# Motherboard_lpcxpresso.net
KiCad netlist of a schematic drawn in EAGLE
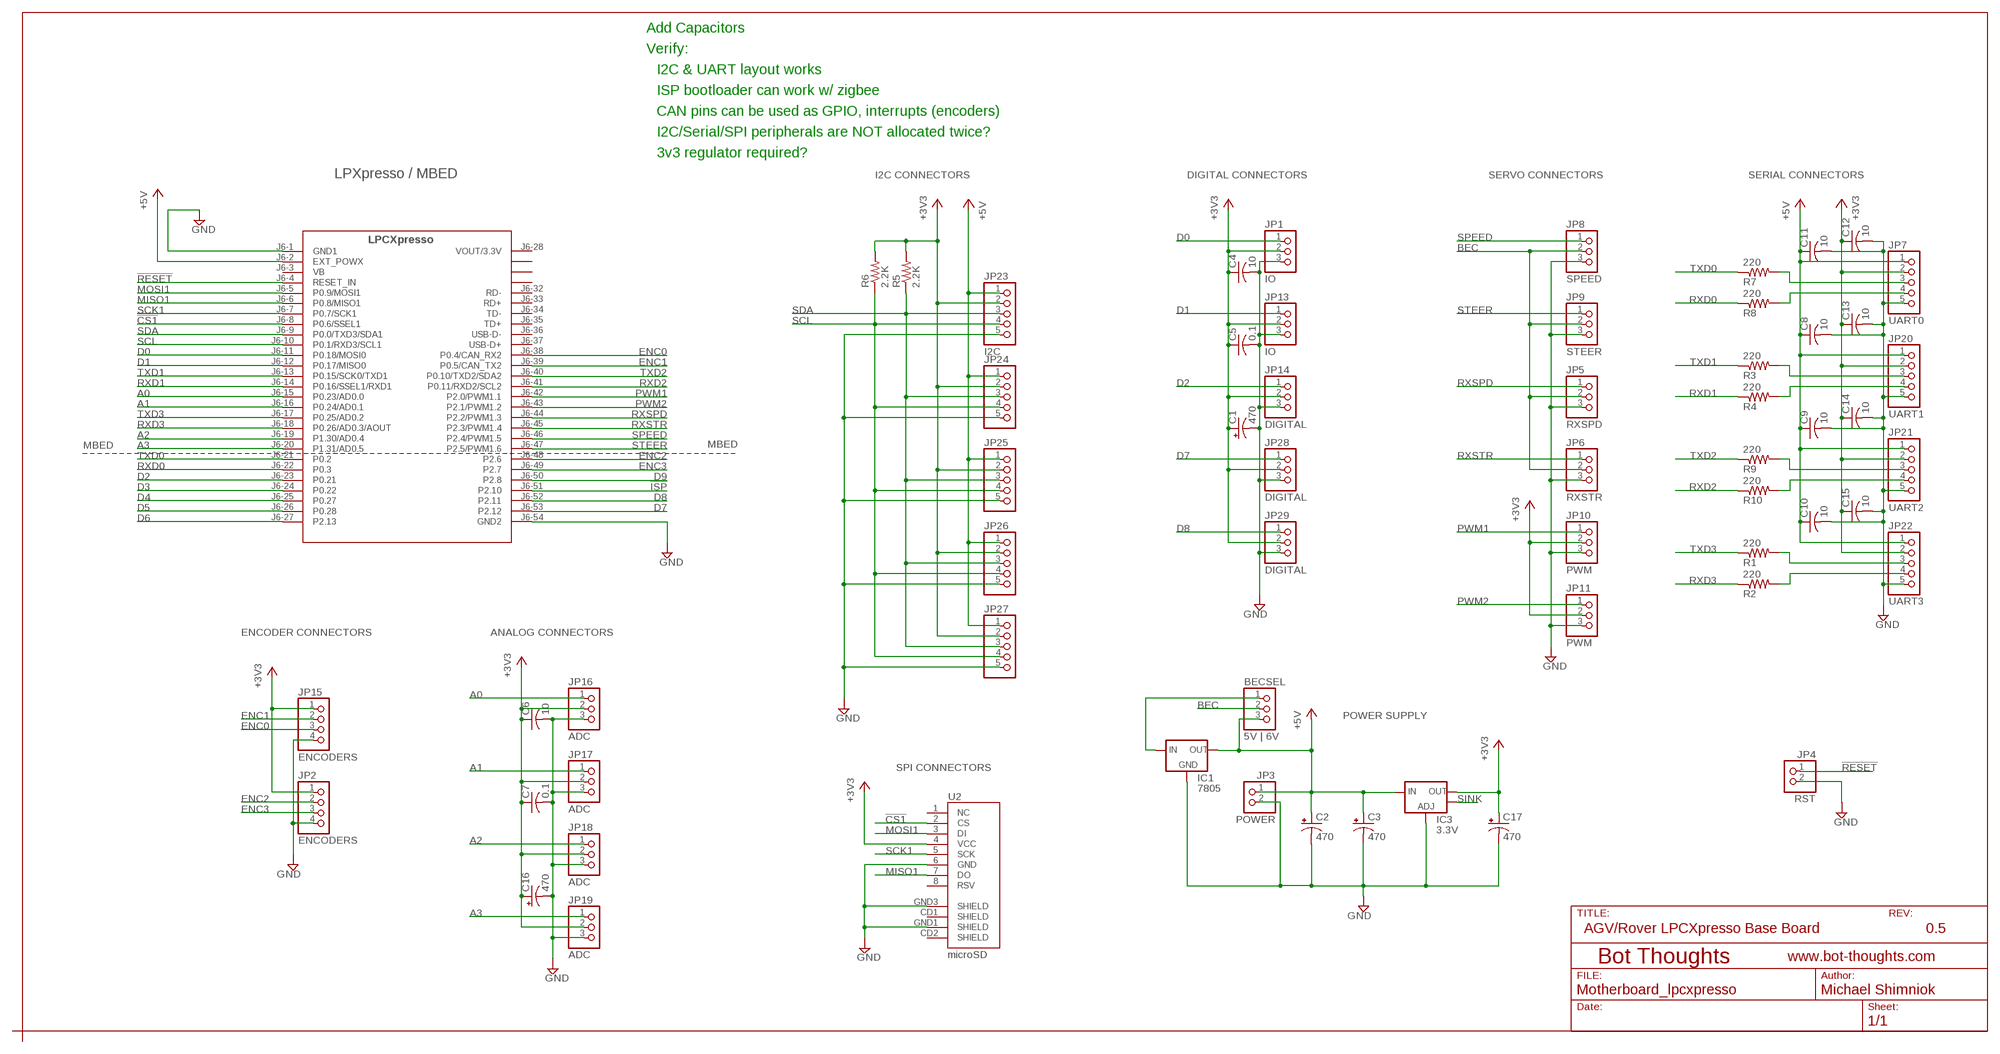
[diagram p0: schematic, sheet 1]

(export (version "E")
  (design (tool "Eeschema 10.0.6"))
  (components
    (comp (ref "BECSEL")
      (value "5V | 6V")
      (footprint "eagle-import:1X03-S")
      (libsource (lib "eagle-import") (part "PINHD-1X03_2.54-S"))
    )
    (comp (ref "C1")
      (value "470")
      (footprint "eagle-import:SMC_C")
      (libsource (lib "eagle-import") (part "CAP_POL_SMC_C"))
    )
    (comp (ref "C2")
      (value "470")
      (footprint "eagle-import:SMC_C")
      (libsource (lib "eagle-import") (part "CAP_POL_SMC_C"))
    )
    (comp (ref "C3")
      (value "470")
      (footprint "eagle-import:SMC_C")
      (libsource (lib "eagle-import") (part "CAP_POL_SMC_C"))
    )
    (comp (ref "C4")
      (value "10")
      (footprint "eagle-import:C0603")
      (libsource (lib "eagle-import") (part "C-USC0603"))
    )
    (comp (ref "C5")
      (value "0.1")
      (footprint "eagle-import:C0603")
      (libsource (lib "eagle-import") (part "C-USC0603"))
    )
    (comp (ref "C6")
      (value "10")
      (footprint "eagle-import:C0603")
      (libsource (lib "eagle-import") (part "C-USC0603"))
    )
    (comp (ref "C7")
      (value "0.1")
      (footprint "eagle-import:C0603")
      (libsource (lib "eagle-import") (part "C-USC0603"))
    )
    (comp (ref "C8")
      (value "10")
      (footprint "eagle-import:C0603")
      (libsource (lib "eagle-import") (part "C-USC0603"))
    )
    (comp (ref "C9")
      (value "10")
      (footprint "eagle-import:C0603")
      (libsource (lib "eagle-import") (part "C-USC0603"))
    )
    (comp (ref "C10")
      (value "10")
      (footprint "eagle-import:C0603")
      (libsource (lib "eagle-import") (part "C-USC0603"))
    )
    (comp (ref "C11")
      (value "10")
      (footprint "eagle-import:C0603")
      (libsource (lib "eagle-import") (part "C-USC0603"))
    )
    (comp (ref "C12")
      (value "10")
      (footprint "eagle-import:C0603")
      (libsource (lib "eagle-import") (part "C-USC0603"))
    )
    (comp (ref "C13")
      (value "10")
      (footprint "eagle-import:C0603")
      (libsource (lib "eagle-import") (part "C-USC0603"))
    )
    (comp (ref "C14")
      (value "10")
      (footprint "eagle-import:C0603")
      (libsource (lib "eagle-import") (part "C-USC0603"))
    )
    (comp (ref "C15")
      (value "10")
      (footprint "eagle-import:C0603")
      (libsource (lib "eagle-import") (part "C-USC0603"))
    )
    (comp (ref "C16")
      (value "470")
      (footprint "eagle-import:SMC_C")
      (libsource (lib "eagle-import") (part "CAP_POL_SMC_C"))
    )
    (comp (ref "C17")
      (value "470")
      (footprint "eagle-import:SMC_C")
      (libsource (lib "eagle-import") (part "CAP_POL_SMC_C"))
    )
    (comp (ref "IC1")
      (value "7805")
      (footprint "eagle-import:78XXS")
      (libsource (lib "eagle-import") (part "78XXS"))
    )
    (comp (ref "IC3")
      (value "3.3V")
      (footprint "eagle-import:SOT223")
      (libsource (lib "eagle-import") (part "V_REG_LM1117SOT223"))
    )
    (comp (ref "JP1")
      (value "IO")
      (footprint "eagle-import:1X03-S")
      (libsource (lib "eagle-import") (part "PINHD-1X03_2.54-S"))
    )
    (comp (ref "JP2")
      (value "ENCODERS")
      (footprint "eagle-import:1X04-S")
      (libsource (lib "eagle-import") (part "PINHD-1X04_2.54-S"))
    )
    (comp (ref "JP3")
      (value "POWER")
      (footprint "eagle-import:1X02-S")
      (libsource (lib "eagle-import") (part "PINHD-1X02_2.54-S"))
    )
    (comp (ref "JP4")
      (value "RST")
      (footprint "eagle-import:1X02-S")
      (libsource (lib "eagle-import") (part "PINHD-1X02_2.54-S"))
    )
    (comp (ref "JP5")
      (value "RXSPD")
      (footprint "eagle-import:1X03-S")
      (libsource (lib "eagle-import") (part "PINHD-1X03_2.54-S"))
    )
    (comp (ref "JP6")
      (value "RXSTR")
      (footprint "eagle-import:1X03-S")
      (libsource (lib "eagle-import") (part "PINHD-1X03_2.54-S"))
    )
    (comp (ref "JP7")
      (value "UART0")
      (footprint "eagle-import:1X05-S")
      (libsource (lib "eagle-import") (part "PINHD-1X05_2.54-S"))
    )
    (comp (ref "JP8")
      (value "SPEED")
      (footprint "eagle-import:1X03-S")
      (libsource (lib "eagle-import") (part "PINHD-1X03_2.54-S"))
    )
    (comp (ref "JP9")
      (value "STEER")
      (footprint "eagle-import:1X03-S")
      (libsource (lib "eagle-import") (part "PINHD-1X03_2.54-S"))
    )
    (comp (ref "JP10")
      (value "PWM")
      (footprint "eagle-import:1X03-S")
      (libsource (lib "eagle-import") (part "PINHD-1X03_2.54-S"))
    )
    (comp (ref "JP11")
      (value "PWM")
      (footprint "eagle-import:1X03-S")
      (libsource (lib "eagle-import") (part "PINHD-1X03_2.54-S"))
    )
    (comp (ref "JP13")
      (value "IO")
      (footprint "eagle-import:1X03-S")
      (libsource (lib "eagle-import") (part "PINHD-1X03_2.54-S"))
    )
    (comp (ref "JP14")
      (value "DIGITAL")
      (footprint "eagle-import:1X03-S")
      (libsource (lib "eagle-import") (part "PINHD-1X03_2.54-S"))
    )
    (comp (ref "JP15")
      (value "ENCODERS")
      (footprint "eagle-import:1X04-S")
      (libsource (lib "eagle-import") (part "PINHD-1X04_2.54-S"))
    )
    (comp (ref "JP16")
      (value "ADC")
      (footprint "eagle-import:1X03-S")
      (libsource (lib "eagle-import") (part "PINHD-1X03_2.54-S"))
    )
    (comp (ref "JP17")
      (value "ADC")
      (footprint "eagle-import:1X03-S")
      (libsource (lib "eagle-import") (part "PINHD-1X03_2.54-S"))
    )
    (comp (ref "JP18")
      (value "ADC")
      (footprint "eagle-import:1X03-S")
      (libsource (lib "eagle-import") (part "PINHD-1X03_2.54-S"))
    )
    (comp (ref "JP19")
      (value "ADC")
      (footprint "eagle-import:1X03-S")
      (libsource (lib "eagle-import") (part "PINHD-1X03_2.54-S"))
    )
    (comp (ref "JP20")
      (value "UART1")
      (footprint "eagle-import:1X05-S")
      (libsource (lib "eagle-import") (part "PINHD-1X05_2.54-S"))
    )
    (comp (ref "JP21")
      (value "UART2")
      (footprint "eagle-import:1X05-S")
      (libsource (lib "eagle-import") (part "PINHD-1X05_2.54-S"))
    )
    (comp (ref "JP22")
      (value "UART3")
      (footprint "eagle-import:1X05-S")
      (libsource (lib "eagle-import") (part "PINHD-1X05_2.54-S"))
    )
    (comp (ref "JP23")
      (value "I2C")
      (footprint "eagle-import:1X05-S")
      (libsource (lib "eagle-import") (part "PINHD-1X05_2.54-S"))
    )
    (comp (ref "JP24")
      (value "PINHD-1X05_2.54-S")
      (footprint "eagle-import:1X05-S")
      (libsource (lib "eagle-import") (part "PINHD-1X05_2.54-S"))
    )
    (comp (ref "JP25")
      (value "PINHD-1X05_2.54-S")
      (footprint "eagle-import:1X05-S")
      (libsource (lib "eagle-import") (part "PINHD-1X05_2.54-S"))
    )
    (comp (ref "JP26")
      (value "PINHD-1X05_2.54-S")
      (footprint "eagle-import:1X05-S")
      (libsource (lib "eagle-import") (part "PINHD-1X05_2.54-S"))
    )
    (comp (ref "JP27")
      (value "PINHD-1X05_2.54-S")
      (footprint "eagle-import:1X05-S")
      (libsource (lib "eagle-import") (part "PINHD-1X05_2.54-S"))
    )
    (comp (ref "JP28")
      (value "DIGITAL")
      (footprint "eagle-import:1X03-S")
      (libsource (lib "eagle-import") (part "PINHD-1X03_2.54-S"))
    )
    (comp (ref "JP29")
      (value "DIGITAL")
      (footprint "eagle-import:1X03-S")
      (libsource (lib "eagle-import") (part "PINHD-1X03_2.54-S"))
    )
    (comp (ref "R1")
      (value "220")
      (footprint "eagle-import:R0603")
      (fields (field (name "MPN") "WCR0805-220RFI"))
      (libsource (lib "eagle-import") (part "R-US_R0603"))
    )
    (comp (ref "R2")
      (value "220")
      (footprint "eagle-import:R0603")
      (fields (field (name "MPN") "WCR0805-220RFI"))
      (libsource (lib "eagle-import") (part "R-US_R0603"))
    )
    (comp (ref "R3")
      (value "220")
      (footprint "eagle-import:R0603")
      (fields (field (name "MPN") "WCR0805-220RFI"))
      (libsource (lib "eagle-import") (part "R-US_R0603"))
    )
    (comp (ref "R4")
      (value "220")
      (footprint "eagle-import:R0603")
      (fields (field (name "MPN") "WCR0805-220RFI"))
      (libsource (lib "eagle-import") (part "R-US_R0603"))
    )
    (comp (ref "R5")
      (value "2.2K")
      (footprint "eagle-import:R0603")
      (libsource (lib "eagle-import") (part "R-US_R0603"))
    )
    (comp (ref "R6")
      (value "2.2K")
      (footprint "eagle-import:R0603")
      (libsource (lib "eagle-import") (part "R-US_R0603"))
    )
    (comp (ref "R7")
      (value "220")
      (footprint "eagle-import:R0603")
      (fields (field (name "MPN") "WCR0805-220RFI"))
      (libsource (lib "eagle-import") (part "R-US_R0603"))
    )
    (comp (ref "R8")
      (value "220")
      (footprint "eagle-import:R0603")
      (fields (field (name "MPN") "WCR0805-220RFI"))
      (libsource (lib "eagle-import") (part "R-US_R0603"))
    )
    (comp (ref "R9")
      (value "220")
      (footprint "eagle-import:R0603")
      (fields (field (name "MPN") "WCR0805-220RFI"))
      (libsource (lib "eagle-import") (part "R-US_R0603"))
    )
    (comp (ref "R10")
      (value "220")
      (footprint "eagle-import:R0603")
      (fields (field (name "MPN") "WCR0805-220RFI"))
      (libsource (lib "eagle-import") (part "R-US_R0603"))
    )
    (comp (ref "U$1")
      (value "LPCXPRESSO")
      (footprint "eagle-import:LPCXPRESSO_NO_PAD")
      (libsource (lib "eagle-import") (part "LPCXPRESSO_NO_PAD_1768_REVB"))
    )
    (comp (ref "U2")
      (value "microSD")
      (footprint "eagle-import:MICRO-SD-SOCKET-PP")
      (libsource (lib "eagle-import") (part "USD-SOCKETNEW"))
    )
  )
  (nets
    (net (code "1") (name "+3V3") (class "Default")
      (node (ref "C1") (pin "+") (pinfunction "+_+") (pintype "passive"))
      (node (ref "C12") (pin "1") (pinfunction "1_1") (pintype "passive"))
      (node (ref "C13") (pin "1") (pinfunction "1_1") (pintype "passive"))
      (node (ref "C14") (pin "1") (pinfunction "1_1") (pintype "passive"))
      (node (ref "C15") (pin "1") (pinfunction "1_1") (pintype "passive"))
      (node (ref "C16") (pin "+") (pinfunction "+_+") (pintype "passive"))
      (node (ref "C17") (pin "+") (pinfunction "+_+") (pintype "passive"))
      (node (ref "C4") (pin "1") (pinfunction "1_1") (pintype "passive"))
      (node (ref "C5") (pin "1") (pinfunction "1_1") (pintype "passive"))
      (node (ref "C6") (pin "1") (pinfunction "1_1") (pintype "passive"))
      (node (ref "C7") (pin "1") (pinfunction "1_1") (pintype "passive"))
      (node (ref "IC3") (pin "2") (pinfunction "OUT_2") (pintype "output"))
      (node (ref "JP1") (pin "2") (pinfunction "2_2") (pintype "passive"))
      (node (ref "JP10") (pin "2") (pinfunction "2_2") (pintype "passive"))
      (node (ref "JP11") (pin "2") (pinfunction "2_2") (pintype "passive"))
      (node (ref "JP13") (pin "2") (pinfunction "2_2") (pintype "passive"))
      (node (ref "JP14") (pin "2") (pinfunction "2_2") (pintype "passive"))
      (node (ref "JP15") (pin "1") (pinfunction "1_1") (pintype "passive"))
      (node (ref "JP16") (pin "2") (pinfunction "2_2") (pintype "passive"))
      (node (ref "JP17") (pin "2") (pinfunction "2_2") (pintype "passive"))
      (node (ref "JP18") (pin "2") (pinfunction "2_2") (pintype "passive"))
      (node (ref "JP19") (pin "2") (pinfunction "2_2") (pintype "passive"))
      (node (ref "JP2") (pin "1") (pinfunction "1_1") (pintype "passive"))
      (node (ref "JP20") (pin "2") (pinfunction "2_2") (pintype "passive"))
      (node (ref "JP21") (pin "2") (pinfunction "2_2") (pintype "passive"))
      (node (ref "JP22") (pin "2") (pinfunction "2_2") (pintype "passive"))
      (node (ref "JP23") (pin "2") (pinfunction "2_2") (pintype "passive"))
      (node (ref "JP24") (pin "2") (pinfunction "2_2") (pintype "passive"))
      (node (ref "JP25") (pin "2") (pinfunction "2_2") (pintype "passive"))
      (node (ref "JP26") (pin "2") (pinfunction "2_2") (pintype "passive"))
      (node (ref "JP27") (pin "2") (pinfunction "2_2") (pintype "passive"))
      (node (ref "JP28") (pin "2") (pinfunction "2_2") (pintype "passive"))
      (node (ref "JP29") (pin "2") (pinfunction "2_2") (pintype "passive"))
      (node (ref "JP7") (pin "2") (pinfunction "2_2") (pintype "passive"))
      (node (ref "R5") (pin "2") (pinfunction "2_2") (pintype "passive"))
      (node (ref "R6") (pin "2") (pinfunction "2_2") (pintype "passive"))
      (node (ref "U2") (pin "4") (pinfunction "VCC_4") (pintype "bidirectional"))
    )
    (net (code "2") (name "+5V") (class "Default")
      (node (ref "BECSEL") (pin "3") (pinfunction "3_3") (pintype "passive"))
      (node (ref "C10") (pin "1") (pinfunction "1_1") (pintype "passive"))
      (node (ref "C11") (pin "1") (pinfunction "1_1") (pintype "passive"))
      (node (ref "C2") (pin "+") (pinfunction "+_+") (pintype "passive"))
      (node (ref "C3") (pin "+") (pinfunction "+_+") (pintype "passive"))
      (node (ref "C8") (pin "1") (pinfunction "1_1") (pintype "passive"))
      (node (ref "C9") (pin "1") (pinfunction "1_1") (pintype "passive"))
      (node (ref "IC1") (pin "OUT") (pinfunction "OUT_OUT") (pintype "passive"))
      (node (ref "IC3") (pin "3") (pinfunction "IN_3") (pintype "input"))
      (node (ref "JP20") (pin "1") (pinfunction "1_1") (pintype "passive"))
      (node (ref "JP21") (pin "1") (pinfunction "1_1") (pintype "passive"))
      (node (ref "JP22") (pin "1") (pinfunction "1_1") (pintype "passive"))
      (node (ref "JP23") (pin "1") (pinfunction "1_1") (pintype "passive"))
      (node (ref "JP24") (pin "1") (pinfunction "1_1") (pintype "passive"))
      (node (ref "JP25") (pin "1") (pinfunction "1_1") (pintype "passive"))
      (node (ref "JP26") (pin "1") (pinfunction "1_1") (pintype "passive"))
      (node (ref "JP27") (pin "1") (pinfunction "1_1") (pintype "passive"))
      (node (ref "JP3") (pin "1") (pinfunction "1_1") (pintype "passive"))
      (node (ref "JP7") (pin "1") (pinfunction "1_1") (pintype "passive"))
      (node (ref "U$1") (pin "J6-2") (pinfunction "EXT_POWX_J6-2") (pintype "bidirectional"))
    )
    (net (code "3") (name "/A0") (class "Default")
      (node (ref "JP16") (pin "1") (pinfunction "1_1") (pintype "passive"))
      (node (ref "U$1") (pin "J6-15") (pinfunction "P0.23/AD0.0_J6-15") (pintype "bidirectional"))
    )
    (net (code "4") (name "/A1") (class "Default")
      (node (ref "JP17") (pin "1") (pinfunction "1_1") (pintype "passive"))
      (node (ref "U$1") (pin "J6-16") (pinfunction "P0.24/AD0.1_J6-16") (pintype "bidirectional"))
    )
    (net (code "5") (name "/A2") (class "Default")
      (node (ref "JP18") (pin "1") (pinfunction "1_1") (pintype "passive"))
      (node (ref "U$1") (pin "J6-19") (pinfunction "P1.30/AD0.4_J6-19") (pintype "bidirectional"))
    )
    (net (code "6") (name "/A3") (class "Default")
      (node (ref "JP19") (pin "1") (pinfunction "1_1") (pintype "passive"))
      (node (ref "U$1") (pin "J6-20") (pinfunction "P1.31/AD0.5_J6-20") (pintype "bidirectional"))
    )
    (net (code "7") (name "/BEC") (class "Default")
      (node (ref "BECSEL") (pin "2") (pinfunction "2_2") (pintype "passive"))
      (node (ref "JP5") (pin "2") (pinfunction "2_2") (pintype "passive"))
      (node (ref "JP6") (pin "2") (pinfunction "2_2") (pintype "passive"))
      (node (ref "JP8") (pin "2") (pinfunction "2_2") (pintype "passive"))
      (node (ref "JP9") (pin "2") (pinfunction "2_2") (pintype "passive"))
    )
    (net (code "8") (name "/D0") (class "Default")
      (node (ref "JP1") (pin "1") (pinfunction "1_1") (pintype "passive"))
      (node (ref "U$1") (pin "J6-11") (pinfunction "P0.18/MOSI0_J6-11") (pintype "bidirectional"))
    )
    (net (code "9") (name "/D1") (class "Default")
      (node (ref "JP13") (pin "1") (pinfunction "1_1") (pintype "passive"))
      (node (ref "U$1") (pin "J6-12") (pinfunction "P0.17/MISO0_J6-12") (pintype "bidirectional"))
    )
    (net (code "10") (name "/D2") (class "Default")
      (node (ref "JP14") (pin "1") (pinfunction "1_1") (pintype "passive"))
      (node (ref "U$1") (pin "J6-23") (pinfunction "P0.21_J6-23") (pintype "bidirectional"))
    )
    (net (code "11") (name "/D3") (class "Default")
      (node (ref "U$1") (pin "J6-24") (pinfunction "P0.22_J6-24") (pintype "bidirectional"))
    )
    (net (code "12") (name "/D4") (class "Default")
      (node (ref "U$1") (pin "J6-25") (pinfunction "P0.27_J6-25") (pintype "bidirectional"))
    )
    (net (code "13") (name "/D5") (class "Default")
      (node (ref "U$1") (pin "J6-26") (pinfunction "P0.28_J6-26") (pintype "bidirectional"))
    )
    (net (code "14") (name "/D6") (class "Default")
      (node (ref "U$1") (pin "J6-27") (pinfunction "P2.13_J6-27") (pintype "bidirectional"))
    )
    (net (code "15") (name "/D7") (class "Default")
      (node (ref "JP28") (pin "1") (pinfunction "1_1") (pintype "passive"))
      (node (ref "U$1") (pin "J6-53") (pinfunction "P2.12_J6-53") (pintype "bidirectional"))
    )
    (net (code "16") (name "/D8") (class "Default")
      (node (ref "JP29") (pin "1") (pinfunction "1_1") (pintype "passive"))
      (node (ref "U$1") (pin "J6-52") (pinfunction "P2.11_J6-52") (pintype "bidirectional"))
    )
    (net (code "17") (name "/D9") (class "Default")
      (node (ref "U$1") (pin "J6-50") (pinfunction "P2.8_J6-50") (pintype "bidirectional"))
    )
    (net (code "18") (name "/ENC0") (class "Default")
      (node (ref "JP15") (pin "3") (pinfunction "3_3") (pintype "passive"))
      (node (ref "U$1") (pin "J6-38") (pinfunction "P0.4/CAN_RX2_J6-38") (pintype "bidirectional"))
    )
    (net (code "19") (name "/ENC1") (class "Default")
      (node (ref "JP15") (pin "2") (pinfunction "2_2") (pintype "passive"))
      (node (ref "U$1") (pin "J6-39") (pinfunction "P0.5/CAN_TX2_J6-39") (pintype "bidirectional"))
    )
    (net (code "20") (name "/ENC2") (class "Default")
      (node (ref "JP2") (pin "2") (pinfunction "2_2") (pintype "passive"))
      (node (ref "U$1") (pin "J6-48") (pinfunction "P2.6_J6-48") (pintype "bidirectional"))
    )
    (net (code "21") (name "/ENC3") (class "Default")
      (node (ref "JP2") (pin "3") (pinfunction "3_3") (pintype "passive"))
      (node (ref "U$1") (pin "J6-49") (pinfunction "P2.7_J6-49") (pintype "bidirectional"))
    )
    (net (code "22") (name "/MISO1") (class "Default")
      (node (ref "U$1") (pin "J6-6") (pinfunction "P0.8/MISO1_J6-6") (pintype "bidirectional"))
      (node (ref "U2") (pin "7") (pinfunction "DO_7") (pintype "bidirectional"))
    )
    (net (code "23") (name "/MOSI1") (class "Default")
      (node (ref "U$1") (pin "J6-5") (pinfunction "P0.9/MOSI1_J6-5") (pintype "bidirectional"))
      (node (ref "U2") (pin "3") (pinfunction "DI_3") (pintype "bidirectional"))
    )
    (net (code "24") (name "/PWM1") (class "Default")
      (node (ref "JP10") (pin "1") (pinfunction "1_1") (pintype "passive"))
      (node (ref "U$1") (pin "J6-42") (pinfunction "P2.0/PWM1.1_J6-42") (pintype "bidirectional"))
    )
    (net (code "25") (name "/PWM2") (class "Default")
      (node (ref "JP11") (pin "1") (pinfunction "1_1") (pintype "passive"))
      (node (ref "U$1") (pin "J6-43") (pinfunction "P2.1/PWM1.2_J6-43") (pintype "bidirectional"))
    )
    (net (code "26") (name "/RXD0") (class "Default")
      (node (ref "R8") (pin "1") (pinfunction "1_1") (pintype "passive"))
      (node (ref "U$1") (pin "J6-22") (pinfunction "P0.3_J6-22") (pintype "bidirectional"))
    )
    (net (code "27") (name "/RXD1") (class "Default")
      (node (ref "R4") (pin "1") (pinfunction "1_1") (pintype "passive"))
      (node (ref "U$1") (pin "J6-14") (pinfunction "P0.16/SSEL1/RXD1_J6-14") (pintype "bidirectional"))
    )
    (net (code "28") (name "/RXD2") (class "Default")
      (node (ref "R10") (pin "1") (pinfunction "1_1") (pintype "passive"))
      (node (ref "U$1") (pin "J6-41") (pinfunction "P0.11/RXD2/SCL2_J6-41") (pintype "bidirectional"))
    )
    (net (code "29") (name "/RXD3") (class "Default")
      (node (ref "R2") (pin "1") (pinfunction "1_1") (pintype "passive"))
      (node (ref "U$1") (pin "J6-18") (pinfunction "P0.26/AD0.3/AOUT_J6-18") (pintype "bidirectional"))
    )
    (net (code "30") (name "/RXSPD") (class "Default")
      (node (ref "JP5") (pin "1") (pinfunction "1_1") (pintype "passive"))
      (node (ref "U$1") (pin "J6-44") (pinfunction "P2.2/PWM1.3_J6-44") (pintype "bidirectional"))
    )
    (net (code "31") (name "/RXSTR") (class "Default")
      (node (ref "JP6") (pin "1") (pinfunction "1_1") (pintype "passive"))
      (node (ref "U$1") (pin "J6-45") (pinfunction "P2.3/PWM1.4_J6-45") (pintype "bidirectional"))
    )
    (net (code "32") (name "/SCK1") (class "Default")
      (node (ref "U$1") (pin "J6-7") (pinfunction "P0.7/SCK1_J6-7") (pintype "bidirectional"))
      (node (ref "U2") (pin "5") (pinfunction "SCK_5") (pintype "bidirectional"))
    )
    (net (code "33") (name "/SCL") (class "Default")
      (node (ref "JP23") (pin "4") (pinfunction "4_4") (pintype "passive"))
      (node (ref "JP24") (pin "4") (pinfunction "4_4") (pintype "passive"))
      (node (ref "JP25") (pin "4") (pinfunction "4_4") (pintype "passive"))
      (node (ref "JP26") (pin "4") (pinfunction "4_4") (pintype "passive"))
      (node (ref "JP27") (pin "4") (pinfunction "4_4") (pintype "passive"))
      (node (ref "R6") (pin "1") (pinfunction "1_1") (pintype "passive"))
      (node (ref "U$1") (pin "J6-10") (pinfunction "P0.1/RXD3/SCL1_J6-10") (pintype "bidirectional"))
    )
    (net (code "34") (name "/SDA") (class "Default")
      (node (ref "JP23") (pin "3") (pinfunction "3_3") (pintype "passive"))
      (node (ref "JP24") (pin "3") (pinfunction "3_3") (pintype "passive"))
      (node (ref "JP25") (pin "3") (pinfunction "3_3") (pintype "passive"))
      (node (ref "JP26") (pin "3") (pinfunction "3_3") (pintype "passive"))
      (node (ref "JP27") (pin "3") (pinfunction "3_3") (pintype "passive"))
      (node (ref "R5") (pin "1") (pinfunction "1_1") (pintype "passive"))
      (node (ref "U$1") (pin "J6-9") (pinfunction "P0.0/TXD3/SDA1_J6-9") (pintype "bidirectional"))
    )
    (net (code "35") (name "/SINK") (class "Default")
      (node (ref "IC3") (pin "4") (pinfunction "OUT_4") (pintype "output"))
    )
    (net (code "36") (name "/SPEED") (class "Default")
      (node (ref "JP8") (pin "1") (pinfunction "1_1") (pintype "passive"))
      (node (ref "U$1") (pin "J6-46") (pinfunction "P2.4/PWM1.5_J6-46") (pintype "bidirectional"))
    )
    (net (code "37") (name "/STEER") (class "Default")
      (node (ref "JP9") (pin "1") (pinfunction "1_1") (pintype "passive"))
      (node (ref "U$1") (pin "J6-47") (pinfunction "P2.5/PWM1.6_J6-47") (pintype "bidirectional"))
    )
    (net (code "38") (name "/TXD0") (class "Default")
      (node (ref "R7") (pin "1") (pinfunction "1_1") (pintype "passive"))
      (node (ref "U$1") (pin "J6-21") (pinfunction "P0.2_J6-21") (pintype "bidirectional"))
    )
    (net (code "39") (name "/TXD1") (class "Default")
      (node (ref "R3") (pin "1") (pinfunction "1_1") (pintype "passive"))
      (node (ref "U$1") (pin "J6-13") (pinfunction "P0.15/SCK0/TXD1_J6-13") (pintype "bidirectional"))
    )
    (net (code "40") (name "/TXD2") (class "Default")
      (node (ref "R9") (pin "1") (pinfunction "1_1") (pintype "passive"))
      (node (ref "U$1") (pin "J6-40") (pinfunction "P0.10/TXD2/SDA2_J6-40") (pintype "bidirectional"))
    )
    (net (code "41") (name "/TXD3") (class "Default")
      (node (ref "R1") (pin "1") (pinfunction "1_1") (pintype "passive"))
      (node (ref "U$1") (pin "J6-17") (pinfunction "P0.25/AD0.2_J6-17") (pintype "bidirectional"))
    )
    (net (code "42") (name "/~{CS1}") (class "Default")
      (node (ref "U$1") (pin "J6-8") (pinfunction "P0.6/SSEL1_J6-8") (pintype "bidirectional"))
      (node (ref "U2") (pin "2") (pinfunction "CS_2") (pintype "bidirectional"))
    )
    (net (code "43") (name "/~{ISP}") (class "Default")
      (node (ref "U$1") (pin "J6-51") (pinfunction "P2.10_J6-51") (pintype "bidirectional"))
    )
    (net (code "44") (name "/~{RESET}") (class "Default")
      (node (ref "JP4") (pin "1") (pinfunction "1_1") (pintype "passive"))
      (node (ref "U$1") (pin "J6-4") (pinfunction "RESET_IN_J6-4") (pintype "bidirectional"))
    )
    (net (code "45") (name "GND") (class "Default")
      (node (ref "C1") (pin "-") (pinfunction "-_-") (pintype "passive"))
      (node (ref "C10") (pin "2") (pinfunction "2_2") (pintype "passive"))
      (node (ref "C11") (pin "2") (pinfunction "2_2") (pintype "passive"))
      (node (ref "C12") (pin "2") (pinfunction "2_2") (pintype "passive"))
      (node (ref "C13") (pin "2") (pinfunction "2_2") (pintype "passive"))
      (node (ref "C14") (pin "2") (pinfunction "2_2") (pintype "passive"))
      (node (ref "C15") (pin "2") (pinfunction "2_2") (pintype "passive"))
      (node (ref "C16") (pin "-") (pinfunction "-_-") (pintype "passive"))
      (node (ref "C17") (pin "-") (pinfunction "-_-") (pintype "passive"))
      (node (ref "C2") (pin "-") (pinfunction "-_-") (pintype "passive"))
      (node (ref "C3") (pin "-") (pinfunction "-_-") (pintype "passive"))
      (node (ref "C4") (pin "2") (pinfunction "2_2") (pintype "passive"))
      (node (ref "C5") (pin "2") (pinfunction "2_2") (pintype "passive"))
      (node (ref "C6") (pin "2") (pinfunction "2_2") (pintype "passive"))
      (node (ref "C7") (pin "2") (pinfunction "2_2") (pintype "passive"))
      (node (ref "C8") (pin "2") (pinfunction "2_2") (pintype "passive"))
      (node (ref "C9") (pin "2") (pinfunction "2_2") (pintype "passive"))
      (node (ref "IC1") (pin "GND") (pinfunction "GND_GND") (pintype "input"))
      (node (ref "IC3") (pin "1") (pinfunction "ADJ_1") (pintype "input"))
      (node (ref "JP1") (pin "3") (pinfunction "3_3") (pintype "passive"))
      (node (ref "JP10") (pin "3") (pinfunction "3_3") (pintype "passive"))
      (node (ref "JP11") (pin "3") (pinfunction "3_3") (pintype "passive"))
      (node (ref "JP13") (pin "3") (pinfunction "3_3") (pintype "passive"))
      (node (ref "JP14") (pin "3") (pinfunction "3_3") (pintype "passive"))
      (node (ref "JP15") (pin "4") (pinfunction "4_4") (pintype "passive"))
      (node (ref "JP16") (pin "3") (pinfunction "3_3") (pintype "passive"))
      (node (ref "JP17") (pin "3") (pinfunction "3_3") (pintype "passive"))
      (node (ref "JP18") (pin "3") (pinfunction "3_3") (pintype "passive"))
      (node (ref "JP19") (pin "3") (pinfunction "3_3") (pintype "passive"))
      (node (ref "JP2") (pin "4") (pinfunction "4_4") (pintype "passive"))
      (node (ref "JP20") (pin "5") (pinfunction "5_5") (pintype "passive"))
      (node (ref "JP21") (pin "5") (pinfunction "5_5") (pintype "passive"))
      (node (ref "JP22") (pin "5") (pinfunction "5_5") (pintype "passive"))
      (node (ref "JP23") (pin "5") (pinfunction "5_5") (pintype "passive"))
      (node (ref "JP24") (pin "5") (pinfunction "5_5") (pintype "passive"))
      (node (ref "JP25") (pin "5") (pinfunction "5_5") (pintype "passive"))
      (node (ref "JP26") (pin "5") (pinfunction "5_5") (pintype "passive"))
      (node (ref "JP27") (pin "5") (pinfunction "5_5") (pintype "passive"))
      (node (ref "JP28") (pin "3") (pinfunction "3_3") (pintype "passive"))
      (node (ref "JP29") (pin "3") (pinfunction "3_3") (pintype "passive"))
      (node (ref "JP3") (pin "2") (pinfunction "2_2") (pintype "passive"))
      (node (ref "JP4") (pin "2") (pinfunction "2_2") (pintype "passive"))
      (node (ref "JP5") (pin "3") (pinfunction "3_3") (pintype "passive"))
      (node (ref "JP6") (pin "3") (pinfunction "3_3") (pintype "passive"))
      (node (ref "JP7") (pin "5") (pinfunction "5_5") (pintype "passive"))
      (node (ref "JP8") (pin "3") (pinfunction "3_3") (pintype "passive"))
      (node (ref "JP9") (pin "3") (pinfunction "3_3") (pintype "passive"))
      (node (ref "U$1") (pin "J6-1") (pinfunction "GND1_J6-1") (pintype "bidirectional"))
      (node (ref "U$1") (pin "J6-54") (pinfunction "GND2_J6-54") (pintype "bidirectional"))
      (node (ref "U2") (pin "6") (pinfunction "GND_6") (pintype "bidirectional"))
      (node (ref "U2") (pin "GND1") (pinfunction "SHIELD_GND1") (pintype "bidirectional"))
      (node (ref "U2") (pin "GND3") (pinfunction "SHIELD_GND3") (pintype "bidirectional"))
    )
    (net (code "46") (name "Net-(BECSEL-Pad1)") (class "Default")
      (node (ref "BECSEL") (pin "1") (pinfunction "1_1") (pintype "passive"))
      (node (ref "IC1") (pin "IN") (pinfunction "IN_IN") (pintype "input"))
    )
    (net (code "47") (name "Net-(JP7-Pad3)") (class "Default")
      (node (ref "JP7") (pin "3") (pinfunction "3_3") (pintype "passive"))
      (node (ref "R7") (pin "2") (pinfunction "2_2") (pintype "passive"))
    )
    (net (code "48") (name "Net-(JP7-Pad4)") (class "Default")
      (node (ref "JP7") (pin "4") (pinfunction "4_4") (pintype "passive"))
      (node (ref "R8") (pin "2") (pinfunction "2_2") (pintype "passive"))
    )
    (net (code "49") (name "Net-(JP20-Pad3)") (class "Default")
      (node (ref "JP20") (pin "3") (pinfunction "3_3") (pintype "passive"))
      (node (ref "R3") (pin "2") (pinfunction "2_2") (pintype "passive"))
    )
    (net (code "50") (name "Net-(JP20-Pad4)") (class "Default")
      (node (ref "JP20") (pin "4") (pinfunction "4_4") (pintype "passive"))
      (node (ref "R4") (pin "2") (pinfunction "2_2") (pintype "passive"))
    )
    (net (code "51") (name "Net-(JP21-Pad3)") (class "Default")
      (node (ref "JP21") (pin "3") (pinfunction "3_3") (pintype "passive"))
      (node (ref "R9") (pin "2") (pinfunction "2_2") (pintype "passive"))
    )
    (net (code "52") (name "Net-(JP21-Pad4)") (class "Default")
      (node (ref "JP21") (pin "4") (pinfunction "4_4") (pintype "passive"))
      (node (ref "R10") (pin "2") (pinfunction "2_2") (pintype "passive"))
    )
    (net (code "53") (name "Net-(JP22-Pad3)") (class "Default")
      (node (ref "JP22") (pin "3") (pinfunction "3_3") (pintype "passive"))
      (node (ref "R1") (pin "2") (pinfunction "2_2") (pintype "passive"))
    )
    (net (code "54") (name "Net-(JP22-Pad4)") (class "Default")
      (node (ref "JP22") (pin "4") (pinfunction "4_4") (pintype "passive"))
      (node (ref "R2") (pin "2") (pinfunction "2_2") (pintype "passive"))
    )
    (net (code "55") (name "unconnected-(U$1-P$24-PadJ6-29)") (class "Default")
      (node (ref "U$1") (pin "J6-29") (pinfunction "P$24_J6-29") (pintype "no_connect"))
    )
    (net (code "56") (name "unconnected-(U$1-P$25-PadJ6-30)") (class "Default")
      (node (ref "U$1") (pin "J6-30") (pinfunction "P$25_J6-30") (pintype "no_connect"))
    )
    (net (code "57") (name "unconnected-(U$1-P$26-PadJ6-31)") (class "Default")
      (node (ref "U$1") (pin "J6-31") (pinfunction "P$26_J6-31") (pintype "no_connect"))
    )
    (net (code "58") (name "unconnected-(U$1-RD+-PadJ6-33)") (class "Default")
      (node (ref "U$1") (pin "J6-33") (pinfunction "RD+_J6-33") (pintype "bidirectional"))
    )
    (net (code "59") (name "unconnected-(U$1-RD--PadJ6-32)") (class "Default")
      (node (ref "U$1") (pin "J6-32") (pinfunction "RD-_J6-32") (pintype "bidirectional"))
    )
    (net (code "60") (name "unconnected-(U$1-TD+-PadJ6-35)") (class "Default")
      (node (ref "U$1") (pin "J6-35") (pinfunction "TD+_J6-35") (pintype "bidirectional"))
    )
    (net (code "61") (name "unconnected-(U$1-TD--PadJ6-34)") (class "Default")
      (node (ref "U$1") (pin "J6-34") (pinfunction "TD-_J6-34") (pintype "bidirectional"))
    )
    (net (code "62") (name "unconnected-(U$1-USB-D+-PadJ6-37)") (class "Default")
      (node (ref "U$1") (pin "J6-37") (pinfunction "USB-D+_J6-37") (pintype "bidirectional"))
    )
    (net (code "63") (name "unconnected-(U$1-USB-D--PadJ6-36)") (class "Default")
      (node (ref "U$1") (pin "J6-36") (pinfunction "USB-D-_J6-36") (pintype "bidirectional"))
    )
    (net (code "64") (name "unconnected-(U$1-VB-PadJ6-3)") (class "Default")
      (node (ref "U$1") (pin "J6-3") (pinfunction "VB_J6-3") (pintype "bidirectional"))
    )
    (net (code "65") (name "unconnected-(U$1-VOUT{slash}3.3V-PadJ6-28)") (class "Default")
      (node (ref "U$1") (pin "J6-28") (pinfunction "VOUT/3.3V_J6-28") (pintype "bidirectional"))
    )
    (net (code "66") (name "unconnected-(U2-NC-Pad1)") (class "Default")
      (node (ref "U2") (pin "1") (pinfunction "NC_1") (pintype "bidirectional"))
    )
    (net (code "67") (name "unconnected-(U2-RSV-Pad8)") (class "Default")
      (node (ref "U2") (pin "8") (pinfunction "RSV_8") (pintype "bidirectional"))
    )
    (net (code "68") (name "unconnected-(U2-SHIELD-PadCD1)") (class "Default")
      (node (ref "U2") (pin "CD1") (pinfunction "SHIELD_CD1") (pintype "bidirectional"))
    )
    (net (code "69") (name "unconnected-(U2-SHIELD-PadCD2)") (class "Default")
      (node (ref "U2") (pin "CD2") (pinfunction "SHIELD_CD2") (pintype "bidirectional"))
    )
  )
)
